# mw_ltb_half_v2_0_0.net
KiCad netlist of a schematic drawn in EAGLE
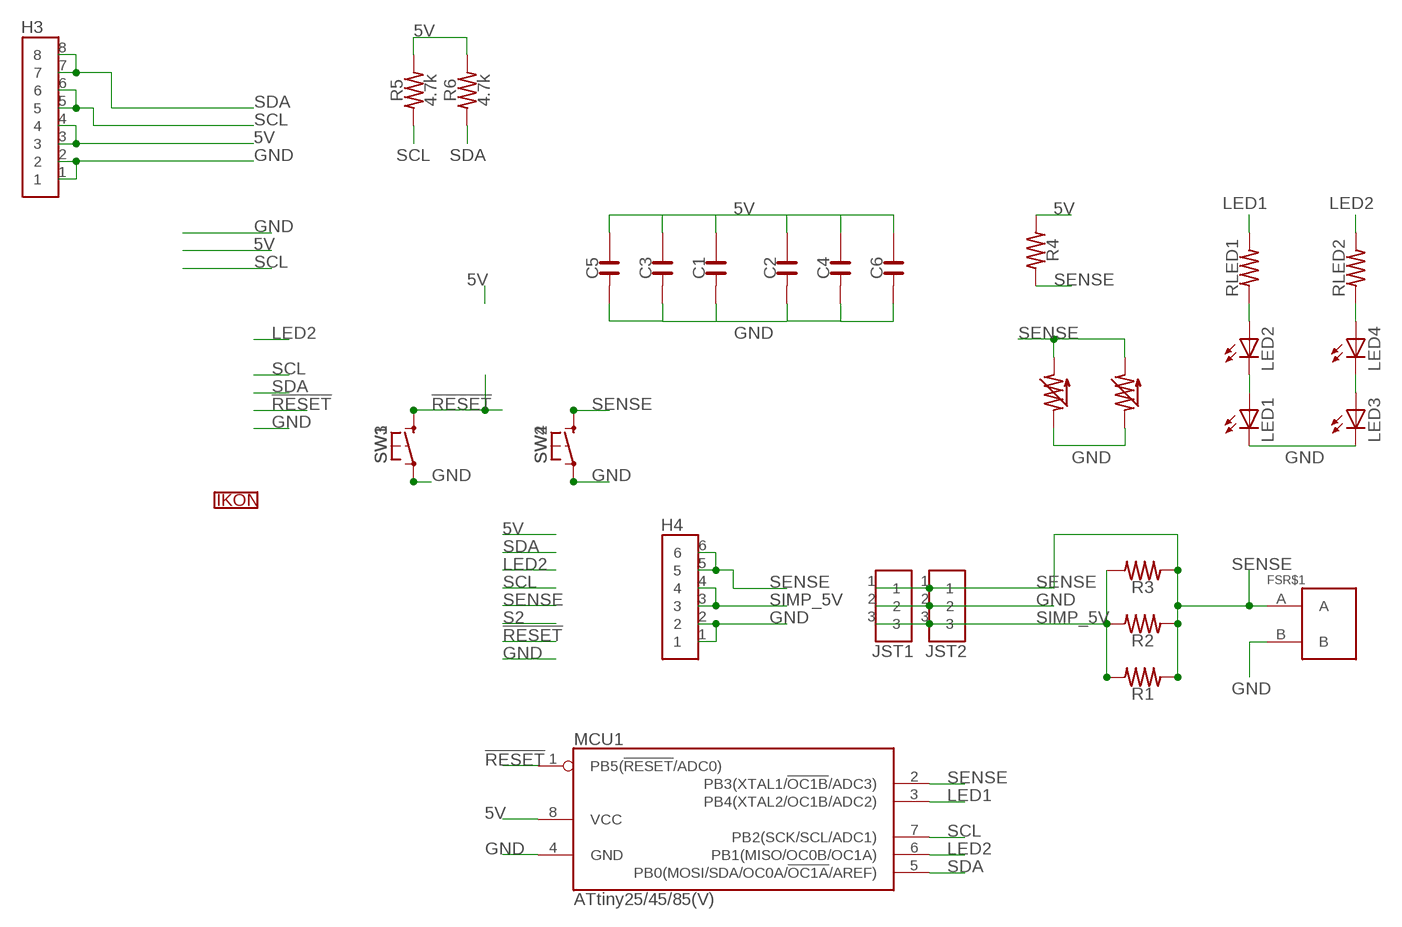
[diagram p0: schematic, sheet 1]

(export (version "E")
  (design (tool "Eeschema 10.0.6"))
  (components
    (comp (ref "C1")
      (value "CAPACITOR-1206")
      (footprint "eagle-import:1206_YAGEO")
      (libsource (lib "eagle-import") (part "CAPACITOR-1206"))
    )
    (comp (ref "C2")
      (value "CAPACITOR-1206")
      (footprint "eagle-import:1206_YAGEO")
      (libsource (lib "eagle-import") (part "CAPACITOR-1206"))
    )
    (comp (ref "C3")
      (value "CAPACITOR-0805")
      (footprint "eagle-import:0805_YAGEO")
      (libsource (lib "eagle-import") (part "CAPACITOR-0805"))
    )
    (comp (ref "C4")
      (value "CAPACITOR-0805")
      (footprint "eagle-import:0805_YAGEO")
      (libsource (lib "eagle-import") (part "CAPACITOR-0805"))
    )
    (comp (ref "C5")
      (value "CAPACITOR-0603")
      (footprint "eagle-import:0603_YAGEO")
      (libsource (lib "eagle-import") (part "CAPACITOR-0603"))
    )
    (comp (ref "C6")
      (value "CAPACITOR-0603")
      (footprint "eagle-import:0603_YAGEO")
      (libsource (lib "eagle-import") (part "CAPACITOR-0603"))
    )
    (comp (ref "FSR$1")
      (value "FSR_PAD88X44_P2B")
      (footprint "eagle-import:FSR_PAD_88X44_P2B")
      (libsource (lib "eagle-import") (part "FSR_PAD88X44_P2B"))
    )
    (comp (ref "H3")
      (value "HEADER_8P-0.1\"_2X4-SMD-SULLINS")
      (footprint "eagle-import:HEADER-0.1__2X4-SMD-SULLINS")
      (libsource (lib "eagle-import") (part "HEADER_8P-0.1{dblquote}_2X4-SMD-SULLINS"))
    )
    (comp (ref "H4")
      (value "HEADER_6P-0.1\"_2X3-SMD-SULLINS")
      (footprint "eagle-import:HEADER-0.1__2X3-SMD-SULLINS")
      (libsource (lib "eagle-import") (part "HEADER_6P-0.1{dblquote}_2X3-SMD-SULLINS"))
    )
    (comp (ref "JST1")
      (value "JST-3-PH-SMD-TOP")
      (footprint "eagle-import:JST_PH_SMD_3_TOP")
      (libsource (lib "eagle-import") (part "JST-3-PH-SMD-TOP"))
    )
    (comp (ref "JST2")
      (value "JST-3-PH-SMD-TOP")
      (footprint "eagle-import:JST_PH_SMD_3_TOP")
      (libsource (lib "eagle-import") (part "JST-3-PH-SMD-TOP"))
    )
    (comp (ref "LED1")
      (value "LED-ZBEND_RM")
      (footprint "eagle-import:Z-BEND_RM")
      (libsource (lib "eagle-import") (part "LED-ZBEND_RM"))
    )
    (comp (ref "LED2")
      (value "LED-ZBEND_RM")
      (footprint "eagle-import:Z-BEND_RM")
      (libsource (lib "eagle-import") (part "LED-ZBEND_RM"))
    )
    (comp (ref "LED3")
      (value "LED-ZBEND_RM")
      (footprint "eagle-import:Z-BEND_RM")
      (libsource (lib "eagle-import") (part "LED-ZBEND_RM"))
    )
    (comp (ref "LED4")
      (value "LED-ZBEND_RM")
      (footprint "eagle-import:Z-BEND_RM")
      (libsource (lib "eagle-import") (part "LED-ZBEND_RM"))
    )
    (comp (ref "MCU1")
      (value "ATMEL_ATTINY25/45/85(V)-SOIC_DUAL")
      (footprint "eagle-import:SOIC-8_DUAL")
      (libsource (lib "eagle-import") (part "ATMEL_ATTINY25/45/85(V)-SOIC_DUAL"))
    )
    (comp (ref "R1")
      (value "RESISTOR-1206")
      (footprint "eagle-import:1206_YAGEO")
      (libsource (lib "eagle-import") (part "RESISTOR-1206"))
    )
    (comp (ref "R2")
      (value "RESISTOR-0805")
      (footprint "eagle-import:0805_YAGEO")
      (libsource (lib "eagle-import") (part "RESISTOR-0805"))
    )
    (comp (ref "R3")
      (value "RESISTOR-0603")
      (footprint "eagle-import:0603_YAGEO")
      (libsource (lib "eagle-import") (part "RESISTOR-0603"))
    )
    (comp (ref "R4")
      (value "RESISTOR-0603")
      (footprint "eagle-import:0603_YAGEO")
      (libsource (lib "eagle-import") (part "RESISTOR-0603"))
    )
    (comp (ref "R5")
      (value "4.7k")
      (footprint "eagle-import:0603_YAGEO")
      (libsource (lib "eagle-import") (part "RESISTOR-0603"))
    )
    (comp (ref "R6")
      (value "4.7k")
      (footprint "eagle-import:0603_YAGEO")
      (libsource (lib "eagle-import") (part "RESISTOR-0603"))
    )
    (comp (ref "RLED1")
      (value "RESISTOR-0603")
      (footprint "eagle-import:0603_YAGEO")
      (libsource (lib "eagle-import") (part "RESISTOR-0603"))
    )
    (comp (ref "RLED2")
      (value "RESISTOR-0603")
      (footprint "eagle-import:0603_YAGEO")
      (libsource (lib "eagle-import") (part "RESISTOR-0603"))
    )
    (comp (ref "SW1")
      (value "SWITCH_SPST-KMT0")
      (footprint "eagle-import:SWITCH_KMT0")
      (libsource (lib "eagle-import") (part "SWITCH_SPST-KMT0"))
    )
    (comp (ref "SW2")
      (value "SWITCH_SPST-KMT0")
      (footprint "eagle-import:SWITCH_KMT0")
      (libsource (lib "eagle-import") (part "SWITCH_SPST-KMT0"))
    )
    (comp (ref "SW3")
      (value "SWITCH_SPST-TL3315")
      (footprint "eagle-import:SWITCH_TL3315")
      (libsource (lib "eagle-import") (part "SWITCH_SPST-TL3315"))
    )
    (comp (ref "SW4")
      (value "SWITCH_SPST-TL3315")
      (footprint "eagle-import:SWITCH_TL3315")
      (libsource (lib "eagle-import") (part "SWITCH_SPST-TL3315"))
    )
    (comp (ref "U$5")
      (value "FSR_PLACE")
      (footprint "eagle-import:FSR_1.5[IN]_SQR")
      (libsource (lib "eagle-import") (part "FSR_PLACE1.5{dblquote}SQR"))
    )
    (comp (ref "U$6")
      (value "FSR_PLACE")
      (footprint "eagle-import:FSR_1.5[IN]_SQR")
      (libsource (lib "eagle-import") (part "FSR_PLACE1.5{dblquote}SQR"))
    )
    (comp (ref "U$9")
      (value "FSR_PINS")
      (footprint "eagle-import:FSR_0.1_-PITCH_PADS-0.05_X0.5_")
      (libsource (lib "eagle-import") (part "FSR_PINSJUMBO_SMD"))
    )
    (comp (ref "U$10")
      (value "FSR_PINS")
      (footprint "eagle-import:FSR_0.1_-PITCH_PADS-0.05_X0.5_")
      (libsource (lib "eagle-import") (part "FSR_PINSJUMBO_SMD"))
    )
    (comp (ref "U$11")
      (value "IKONLEARNING-20MIL")
      (footprint "eagle-import:IKON_LEARNING_20MIL")
      (libsource (lib "eagle-import") (part "IKONLEARNING-20MIL"))
    )
  )
  (nets
    (net (code "1") (name "/5V") (class "Default")
      (node (ref "C1") (pin "2") (pinfunction "P$2_2") (pintype "passive"))
      (node (ref "C2") (pin "2") (pinfunction "P$2_2") (pintype "passive"))
      (node (ref "C3") (pin "2") (pinfunction "P$2_2") (pintype "passive"))
      (node (ref "C4") (pin "2") (pinfunction "P$2_2") (pintype "passive"))
      (node (ref "C5") (pin "2") (pinfunction "P$2_2") (pintype "passive"))
      (node (ref "C6") (pin "2") (pinfunction "P$2_2") (pintype "passive"))
      (node (ref "H3") (pin "3") (pinfunction "3_3") (pintype "bidirectional"))
      (node (ref "H3") (pin "4") (pinfunction "4_4") (pintype "bidirectional"))
      (node (ref "MCU1") (pin "8") (pinfunction "VCC_8") (pintype "bidirectional"))
      (node (ref "R4") (pin "1") (pinfunction "1_1") (pintype "passive"))
      (node (ref "R5") (pin "2") (pinfunction "2_2") (pintype "passive"))
      (node (ref "R6") (pin "2") (pinfunction "2_2") (pintype "passive"))
    )
    (net (code "2") (name "/GND") (class "Default")
      (node (ref "C1") (pin "1") (pinfunction "P$1_1") (pintype "passive"))
      (node (ref "C2") (pin "1") (pinfunction "P$1_1") (pintype "passive"))
      (node (ref "C3") (pin "1") (pinfunction "P$1_1") (pintype "passive"))
      (node (ref "C4") (pin "1") (pinfunction "P$1_1") (pintype "passive"))
      (node (ref "C5") (pin "1") (pinfunction "P$1_1") (pintype "passive"))
      (node (ref "C6") (pin "1") (pinfunction "P$1_1") (pintype "passive"))
      (node (ref "FSR$1") (pin "B") (pinfunction "B_B") (pintype "bidirectional"))
      (node (ref "H3") (pin "1") (pinfunction "1_1") (pintype "bidirectional"))
      (node (ref "H3") (pin "2") (pinfunction "2_2") (pintype "bidirectional"))
      (node (ref "H4") (pin "1") (pinfunction "1_1") (pintype "bidirectional"))
      (node (ref "H4") (pin "2") (pinfunction "2_2") (pintype "bidirectional"))
      (node (ref "JST1") (pin "2") (pinfunction "2_2") (pintype "bidirectional"))
      (node (ref "JST2") (pin "2") (pinfunction "2_2") (pintype "bidirectional"))
      (node (ref "LED1") (pin "K") (pinfunction "C_K") (pintype "passive"))
      (node (ref "LED3") (pin "K") (pinfunction "C_K") (pintype "passive"))
      (node (ref "MCU1") (pin "4") (pinfunction "GND_4") (pintype "bidirectional"))
      (node (ref "SW1") (pin "2@1") (pinfunction "2_2@1") (pintype "passive"))
      (node (ref "SW1") (pin "2@2") (pinfunction "2_2@2") (pintype "passive"))
      (node (ref "SW2") (pin "2@1") (pinfunction "2_2@1") (pintype "passive"))
      (node (ref "SW2") (pin "2@2") (pinfunction "2_2@2") (pintype "passive"))
      (node (ref "SW3") (pin "2@1") (pinfunction "2_2@1") (pintype "passive"))
      (node (ref "SW3") (pin "2@2") (pinfunction "2_2@2") (pintype "passive"))
      (node (ref "SW4") (pin "2@1") (pinfunction "2_2@1") (pintype "passive"))
      (node (ref "SW4") (pin "2@2") (pinfunction "2_2@2") (pintype "passive"))
      (node (ref "U$10") (pin "P$1") (pinfunction "P$1_P$1") (pintype "bidirectional"))
      (node (ref "U$9") (pin "P$2") (pinfunction "P$2_P$2") (pintype "bidirectional"))
    )
    (net (code "3") (name "/LED1") (class "Default")
      (node (ref "MCU1") (pin "3") (pinfunction "PB4(XTAL2/OC1B/ADC2)_3") (pintype "bidirectional"))
      (node (ref "RLED1") (pin "2") (pinfunction "2_2") (pintype "passive"))
    )
    (net (code "4") (name "/LED2") (class "Default")
      (node (ref "MCU1") (pin "6") (pinfunction "PB1(MISO/OC0B/OC1A)_6") (pintype "bidirectional"))
      (node (ref "RLED2") (pin "2") (pinfunction "2_2") (pintype "passive"))
    )
    (net (code "6") (name "/SCL") (class "Default")
      (node (ref "H3") (pin "5") (pinfunction "5_5") (pintype "bidirectional"))
      (node (ref "H3") (pin "6") (pinfunction "6_6") (pintype "bidirectional"))
      (node (ref "MCU1") (pin "7") (pinfunction "PB2(SCK/SCL/ADC1)_7") (pintype "bidirectional"))
      (node (ref "R5") (pin "1") (pinfunction "1_1") (pintype "passive"))
    )
    (net (code "7") (name "/SDA") (class "Default")
      (node (ref "H3") (pin "7") (pinfunction "7_7") (pintype "bidirectional"))
      (node (ref "H3") (pin "8") (pinfunction "8_8") (pintype "bidirectional"))
      (node (ref "MCU1") (pin "5") (pinfunction "PB0(MOSI/SDA/OC0A/~{OC1A}/AREF)_5") (pintype "bidirectional"))
      (node (ref "R6") (pin "1") (pinfunction "1_1") (pintype "passive"))
    )
    (net (code "8") (name "/SENSE") (class "Default")
      (node (ref "FSR$1") (pin "A") (pinfunction "A_A") (pintype "bidirectional"))
      (node (ref "H4") (pin "5") (pinfunction "5_5") (pintype "bidirectional"))
      (node (ref "H4") (pin "6") (pinfunction "6_6") (pintype "bidirectional"))
      (node (ref "JST1") (pin "1") (pinfunction "1_1") (pintype "bidirectional"))
      (node (ref "JST2") (pin "1") (pinfunction "1_1") (pintype "bidirectional"))
      (node (ref "MCU1") (pin "2") (pinfunction "PB3(XTAL1/~{OC1B}/ADC3)_2") (pintype "bidirectional"))
      (node (ref "R1") (pin "1") (pinfunction "1_1") (pintype "passive"))
      (node (ref "R2") (pin "1") (pinfunction "1_1") (pintype "passive"))
      (node (ref "R3") (pin "1") (pinfunction "1_1") (pintype "passive"))
      (node (ref "R4") (pin "2") (pinfunction "2_2") (pintype "passive"))
      (node (ref "SW2") (pin "1@1") (pinfunction "1_1@1") (pintype "passive"))
      (node (ref "SW2") (pin "1@2") (pinfunction "1_1@2") (pintype "passive"))
      (node (ref "SW4") (pin "1@1") (pinfunction "1_1@1") (pintype "passive"))
      (node (ref "SW4") (pin "1@2") (pinfunction "1_1@2") (pintype "passive"))
      (node (ref "U$10") (pin "P$2") (pinfunction "P$2_P$2") (pintype "bidirectional"))
      (node (ref "U$9") (pin "P$1") (pinfunction "P$1_P$1") (pintype "bidirectional"))
    )
    (net (code "9") (name "/SIMP_5V") (class "Default")
      (node (ref "H4") (pin "3") (pinfunction "3_3") (pintype "bidirectional"))
      (node (ref "H4") (pin "4") (pinfunction "4_4") (pintype "bidirectional"))
      (node (ref "JST1") (pin "3") (pinfunction "3_3") (pintype "bidirectional"))
      (node (ref "JST2") (pin "3") (pinfunction "3_3") (pintype "bidirectional"))
      (node (ref "R1") (pin "2") (pinfunction "2_2") (pintype "passive"))
      (node (ref "R2") (pin "2") (pinfunction "2_2") (pintype "passive"))
      (node (ref "R3") (pin "2") (pinfunction "2_2") (pintype "passive"))
    )
    (net (code "10") (name "/~{RESET}") (class "Default")
      (node (ref "MCU1") (pin "1") (pinfunction "PB5(~{RESET}/ADC0)_1") (pintype "bidirectional"))
      (node (ref "SW1") (pin "1@1") (pinfunction "1_1@1") (pintype "passive"))
      (node (ref "SW1") (pin "1@2") (pinfunction "1_1@2") (pintype "passive"))
      (node (ref "SW3") (pin "1@1") (pinfunction "1_1@1") (pintype "passive"))
      (node (ref "SW3") (pin "1@2") (pinfunction "1_1@2") (pintype "passive"))
    )
    (net (code "11") (name "Net-(LED2-C)") (class "Default")
      (node (ref "LED1") (pin "A") (pinfunction "A_A") (pintype "passive"))
      (node (ref "LED2") (pin "K") (pinfunction "C_K") (pintype "passive"))
    )
    (net (code "12") (name "Net-(LED2-PadA)") (class "Default")
      (node (ref "LED2") (pin "A") (pinfunction "A_A") (pintype "passive"))
      (node (ref "RLED1") (pin "1") (pinfunction "1_1") (pintype "passive"))
    )
    (net (code "13") (name "Net-(LED4-C)") (class "Default")
      (node (ref "LED3") (pin "A") (pinfunction "A_A") (pintype "passive"))
      (node (ref "LED4") (pin "K") (pinfunction "C_K") (pintype "passive"))
    )
    (net (code "14") (name "Net-(LED4-PadA)") (class "Default")
      (node (ref "LED4") (pin "A") (pinfunction "A_A") (pintype "passive"))
      (node (ref "RLED2") (pin "1") (pinfunction "1_1") (pintype "passive"))
    )
  )
)
